# RFR24_AMS_Design_-_Fault_V1.net
KiCad netlist of a schematic drawn in Altium Designer
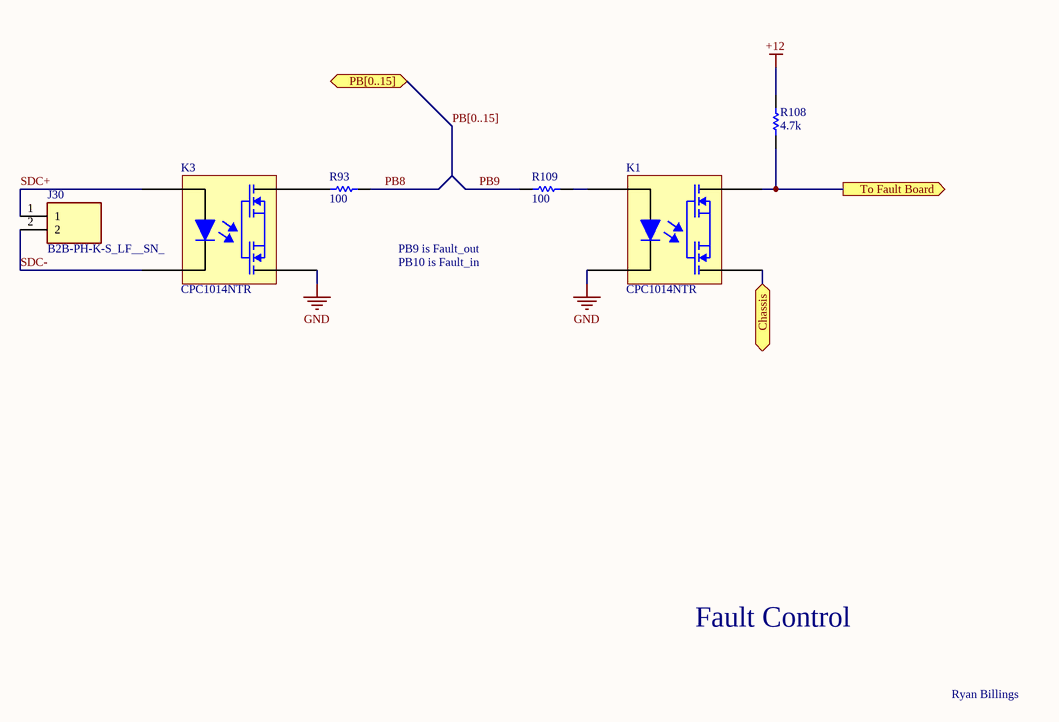
[diagram p0: RFR24 AMS Design - Fault V1.SchDoc]

(export (version "E")
  (design (tool "Eeschema 10.0.6"))
  (components
    (comp (ref "J30")
      (value "B2B-PH-K-S_LF__SN_")
      (footprint "SamacSys:SHDR2W50P0X200_1X2_590X450X600P")
      (description "Connector")
      (fields (field (name "MANUFACTURER_PART_NUMBER") "B2B-PH-K-S(LF)(SN)"))
      (libsource (lib "*") (part "B2B-PH-K-S_LF__SN_"))
    )
    (comp (ref "K1")
      (value "CPC1014NTR")
      (footprint "CPC1014")
      (description "SSR RELAY SPST-NO (1 Form A) 4-SOP (0.150\", 3.81mm)")
      (libsource (lib "Rutgers University") (part "IXYS CPC1014NTR"))
    )
    (comp (ref "K3")
      (value "CPC1014NTR")
      (footprint "CPC1014")
      (description "SSR RELAY SPST-NO (1 Form A) 4-SOP (0.150\", 3.81mm)")
      (libsource (lib "Rutgers University") (part "IXYS CPC1014NTR"))
    )
    (comp (ref "R93")
      (value "100")
      (footprint "RESC2013X70X40LL20T20")
      (description "Chip Resistor, 1 KOhm, +/- 1%, 0.125 W, -55 to 155 degC, 0805 (2013 Metric)")
      (fields (field (name "TOLERANCE") "1%") (field (name "POWER") "125mW"))
      (libsource (lib "Rutgers University") (part "RES-2"))
    )
    (comp (ref "R108")
      (value "4.7k")
      (footprint "RESC2013X70X40LL20T20")
      (description "Chip Resistor, 1 KOhm, +/- 1%, 0.125 W, -55 to 155 degC, 0805 (2013 Metric)")
      (fields (field (name "TOLERANCE") "1%") (field (name "POWER") "125mW"))
      (libsource (lib "Rutgers University") (part "RES-2"))
    )
    (comp (ref "R109")
      (value "100")
      (footprint "RESC2013X70X40LL20T20")
      (description "Chip Resistor, 1 KOhm, +/- 1%, 0.125 W, -55 to 155 degC, 0805 (2013 Metric)")
      (fields (field (name "TOLERANCE") "1%") (field (name "POWER") "125mW"))
      (libsource (lib "Rutgers University") (part "RES-2"))
    )
  )
  (nets
    (net (code "15") (name "+12") (class "Default")
      (node (ref "R108") (pin "2") (pinfunction "2_2") (pintype "passive"))
    )
    (net (code "16") (name "/Chassis") (class "Default")
      (node (ref "K1") (pin "3") (pinfunction "3_3") (pintype "passive"))
    )
    (net (code "17") (name "/PB8") (class "Default")
      (node (ref "R93") (pin "1") (pinfunction "1_1") (pintype "passive"))
    )
    (net (code "18") (name "/PB9") (class "Default")
      (node (ref "R109") (pin "2") (pinfunction "2_2") (pintype "passive"))
    )
    (net (code "20") (name "/SDC+") (class "Default")
      (node (ref "J30") (pin "1") (pinfunction "1_1") (pintype "passive"))
      (node (ref "K3") (pin "1") (pinfunction "1_1") (pintype "passive"))
    )
    (net (code "21") (name "/SDC-") (class "Default")
      (node (ref "J30") (pin "2") (pinfunction "2_2") (pintype "passive"))
      (node (ref "K3") (pin "2") (pinfunction "2_2") (pintype "passive"))
    )
    (net (code "22") (name "/To Fault Board") (class "Default")
      (node (ref "K1") (pin "4") (pinfunction "4_4") (pintype "passive"))
      (node (ref "R108") (pin "1") (pinfunction "1_1") (pintype "passive"))
    )
    (net (code "23") (name "GND") (class "Default")
      (node (ref "K1") (pin "2") (pinfunction "2_2") (pintype "passive"))
      (node (ref "K3") (pin "3") (pinfunction "3_3") (pintype "passive"))
    )
    (net (code "24") (name "Net-(K1-Pad1)") (class "Default")
      (node (ref "K1") (pin "1") (pinfunction "1_1") (pintype "passive"))
      (node (ref "R109") (pin "1") (pinfunction "1_1") (pintype "passive"))
    )
    (net (code "25") (name "Net-(K3-Pad4)") (class "Default")
      (node (ref "K3") (pin "4") (pinfunction "4_4") (pintype "passive"))
      (node (ref "R93") (pin "2") (pinfunction "2_2") (pintype "passive"))
    )
  )
)
